# LED_Driver_-_4.net
KiCad netlist of a schematic drawn in Altium Designer
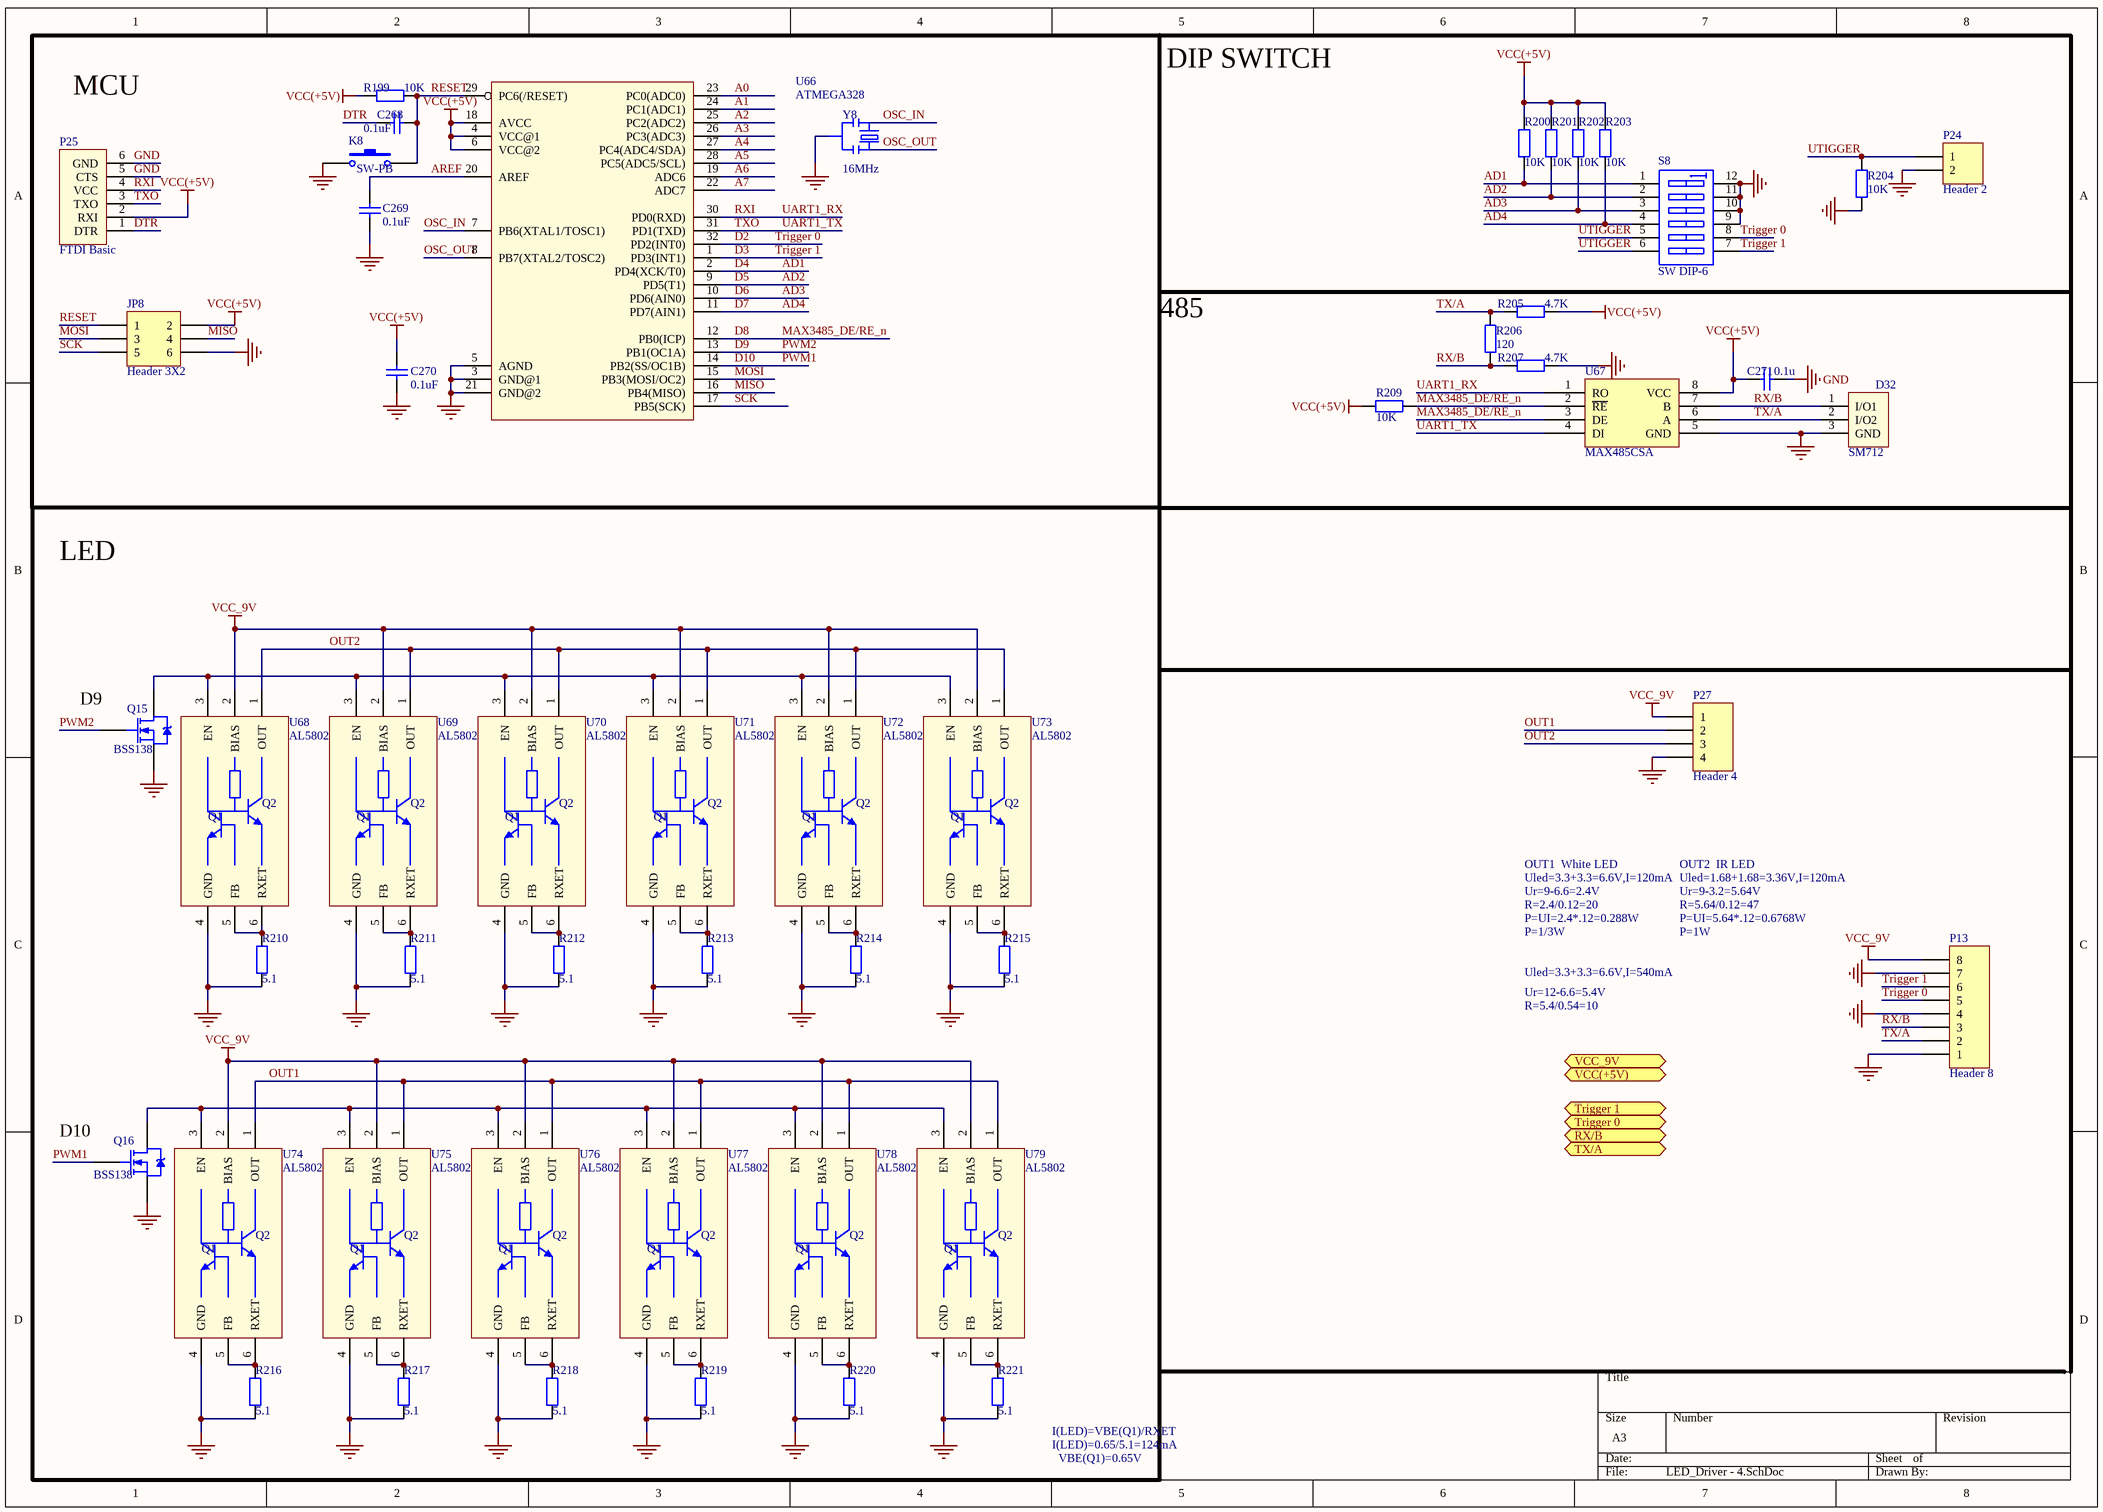
[diagram p0: LED_Driver - 4.SchDoc]

(export (version "E")
  (design (tool "Eeschema 10.0.6"))
  (components
    (comp (ref "C268")
      (value "0.1uF")
      (footprint "C0603")
      (description "Capacitor")
      (fields (field (name "IPARTNUMBER") "C100nF25V10%X7R") (field (name "VOLTAGE") "25V"))
      (libsource (lib "Schlib1") (part "CAP SMT C100nF25V10%X7R"))
    )
    (comp (ref "C269")
      (value "0.1uF")
      (footprint "C0603")
      (description "Capacitor")
      (fields (field (name "IPARTNUMBER") "C100nF25V10%X7R") (field (name "VOLTAGE") "25V"))
      (libsource (lib "Schlib1") (part "CAP SMT C100nF25V10%X7R"))
    )
    (comp (ref "C270")
      (value "0.1uF")
      (footprint "C0603")
      (description "Capacitor")
      (fields (field (name "IPARTNUMBER") "C100nF25V10%X7R") (field (name "VOLTAGE") "25V"))
      (libsource (lib "Schlib1") (part "CAP SMT C100nF25V10%X7R"))
    )
    (comp (ref "C271")
      (value "0.1u")
      (footprint "C0603")
      (description "Capacitor")
      (fields (field (name "PUBLISHER") "Altium Limited"))
      (libsource (lib "Miscellaneous Devices") (part "Cap"))
    )
    (comp (ref "D32")
      (value "SM712")
      (footprint "SOT23-3")
      (libsource (lib "STM32F4_CAM V2.0") (part "SM712"))
    )
    (comp (ref "JP8")
      (value "Header 3X2")
      (footprint "MHDR1X6")
      (description "Header, 3-Pin, Dual row")
      (fields (field (name "PUBLISHER") "Altium Limited"))
      (libsource (lib "Miscellaneous Connectors") (part "Header 3X2"))
    )
    (comp (ref "K8")
      (value "SW-PB")
      (footprint "157SW")
      (description "Switch")
      (fields (field (name "PUBLISHER") "Altium Limited"))
      (libsource (lib "Miscellaneous Devices") (part "SW-PB"))
    )
    (comp (ref "P13")
      (value "Header 8")
      (footprint "SH_1.25MM*8")
      (description "Header, 8-Pin")
      (fields (field (name "PUBLISHER") "Altium Limited"))
      (libsource (lib "Miscellaneous Connectors") (part "Header 8"))
    )
    (comp (ref "P24")
      (value "Header 2")
      (footprint "HDR1X2")
      (description "Header, 2-Pin")
      (fields (field (name "PUBLISHER") "Altium Limited"))
      (libsource (lib "Miscellaneous Connectors") (part "Header 2"))
    )
    (comp (ref "P25")
      (value "FTDI Basic")
      (footprint "MHDR1X6")
      (libsource (lib "PCB_Project1") (part "ARDUINO_SERIAL_PROGRAMPTH"))
    )
    (comp (ref "P27")
      (value "Header 4")
      (footprint "SMT_1.25MM*4")
      (description "Header, 4-Pin")
      (fields (field (name "PUBLISHER") "Altium Limited"))
      (libsource (lib "Miscellaneous Connectors") (part "Header 4"))
    )
    (comp (ref "Q15")
      (value "BSS138")
      (footprint "SOT-23 (Standard)")
      (fields
        (field (name "MANUFACTURER") "Fairchild Semiconductor")
        (field (name "MANUFACTURER PART NUMBER") "BSS123")
      )
      (libsource (lib "Miscellaneous_Devices") (part "NMOS"))
    )
    (comp (ref "Q16")
      (value "BSS138")
      (footprint "SOT-23 (Standard)")
      (fields
        (field (name "MANUFACTURER") "Fairchild Semiconductor")
        (field (name "MANUFACTURER PART NUMBER") "BSS123")
      )
      (libsource (lib "Miscellaneous_Devices") (part "NMOS"))
    )
    (comp (ref "R199")
      (value "10K")
      (footprint "R0603")
      (description "Resistor")
      (libsource (lib "") (part "Res2_2"))
    )
    (comp (ref "R200")
      (value "10K")
      (footprint "R0603")
      (description "Resistor")
      (libsource (lib "") (part "Res2_1"))
    )
    (comp (ref "R201")
      (value "10K")
      (footprint "R0603")
      (description "Resistor")
      (libsource (lib "") (part "Res2_1"))
    )
    (comp (ref "R202")
      (value "10K")
      (footprint "R0603")
      (description "Resistor")
      (libsource (lib "") (part "Res2_1"))
    )
    (comp (ref "R203")
      (value "10K")
      (footprint "R0603")
      (description "Resistor")
      (libsource (lib "") (part "Res2_1"))
    )
    (comp (ref "R204")
      (value "10K")
      (footprint "R0603")
      (description "Resistor")
      (fields (field (name "PUBLISHER") "Altium Limited"))
      (libsource (lib "Miscellaneous Devices") (part "Res2"))
    )
    (comp (ref "R205")
      (value "4.7K")
      (footprint "R0603")
      (description "Resistor")
      (libsource (lib "DM642") (part "Res2"))
    )
    (comp (ref "R206")
      (value "120")
      (footprint "R0603")
      (description "Resistor")
      (libsource (lib "") (part "Res2_1"))
    )
    (comp (ref "R207")
      (value "4.7K")
      (footprint "R0603")
      (description "Resistor")
      (libsource (lib "DM642") (part "Res2"))
    )
    (comp (ref "R209")
      (value "10K")
      (footprint "R0603")
      (description "Resistor")
      (libsource (lib "DM642") (part "Res2"))
    )
    (comp (ref "R210")
      (value "5.1")
      (footprint "R0603")
      (description "Resistor")
      (libsource (lib "") (part "Res2_1"))
    )
    (comp (ref "R211")
      (value "5.1")
      (footprint "R0603")
      (description "Resistor")
      (libsource (lib "") (part "Res2_1"))
    )
    (comp (ref "R212")
      (value "5.1")
      (footprint "R0603")
      (description "Resistor")
      (libsource (lib "") (part "Res2_1"))
    )
    (comp (ref "R213")
      (value "5.1")
      (footprint "R0603")
      (description "Resistor")
      (libsource (lib "") (part "Res2_1"))
    )
    (comp (ref "R214")
      (value "5.1")
      (footprint "R0603")
      (description "Resistor")
      (libsource (lib "") (part "Res2_1"))
    )
    (comp (ref "R215")
      (value "5.1")
      (footprint "R0603")
      (description "Resistor")
      (libsource (lib "") (part "Res2_1"))
    )
    (comp (ref "R216")
      (value "5.1")
      (footprint "R0603")
      (description "Resistor")
      (libsource (lib "") (part "Res2_1"))
    )
    (comp (ref "R217")
      (value "5.1")
      (footprint "R0603")
      (description "Resistor")
      (libsource (lib "") (part "Res2_1"))
    )
    (comp (ref "R218")
      (value "5.1")
      (footprint "R0603")
      (description "Resistor")
      (libsource (lib "") (part "Res2_1"))
    )
    (comp (ref "R219")
      (value "5.1")
      (footprint "R0603")
      (description "Resistor")
      (libsource (lib "") (part "Res2_1"))
    )
    (comp (ref "R220")
      (value "5.1")
      (footprint "R0603")
      (description "Resistor")
      (libsource (lib "") (part "Res2_1"))
    )
    (comp (ref "R221")
      (value "5.1")
      (footprint "R0603")
      (description "Resistor")
      (libsource (lib "") (part "Res2_1"))
    )
    (comp (ref "S8")
      (value "SW DIP-6")
      (footprint "DIP_SW_6WAY_SMD")
      (description "DIP Switch, 6 Position, SPST")
      (fields (field (name "PUBLISHER") "Altium Limited"))
      (libsource (lib "Miscellaneous Devices") (part "SW DIP-6"))
    )
    (comp (ref "U66")
      (value "ATMEGA328")
      (footprint "TQFP32-08")
      (libsource (lib "PCB_Project1") (part "ATMEGA168"))
    )
    (comp (ref "U67")
      (value "MAX485CSA")
      (footprint "SOIC-8")
      (libsource (lib "STM32F4_CAM V1.2") (part "MAX3485CSA"))
    )
    (comp (ref "U68") (value "AL5802") (footprint "SOT26") (libsource (lib "LED") (part "AL5802")))
    (comp (ref "U69") (value "AL5802") (footprint "SOT26") (libsource (lib "LED") (part "AL5802")))
    (comp (ref "U70") (value "AL5802") (footprint "SOT26") (libsource (lib "LED") (part "AL5802")))
    (comp (ref "U71") (value "AL5802") (footprint "SOT26") (libsource (lib "LED") (part "AL5802")))
    (comp (ref "U72") (value "AL5802") (footprint "SOT26") (libsource (lib "LED") (part "AL5802")))
    (comp (ref "U73") (value "AL5802") (footprint "SOT26") (libsource (lib "LED") (part "AL5802")))
    (comp (ref "U74") (value "AL5802") (footprint "SOT26") (libsource (lib "LED") (part "AL5802")))
    (comp (ref "U75") (value "AL5802") (footprint "SOT26") (libsource (lib "LED") (part "AL5802")))
    (comp (ref "U76") (value "AL5802") (footprint "SOT26") (libsource (lib "LED") (part "AL5802")))
    (comp (ref "U77") (value "AL5802") (footprint "SOT26") (libsource (lib "LED") (part "AL5802")))
    (comp (ref "U78") (value "AL5802") (footprint "SOT26") (libsource (lib "LED") (part "AL5802")))
    (comp (ref "U79") (value "AL5802") (footprint "SOT26") (libsource (lib "LED") (part "AL5802")))
    (comp (ref "Y8")
      (value "16MHz")
      (footprint "RESONATOR-SMD")
      (libsource (lib "SparkFun") (part "RESONATORSMD"))
    )
  )
  (nets
    (net (code "1") (name "/A0") (class "Default")
      (node (ref "U66") (pin "23") (pinfunction "PC0(ADC0)_23") (pintype "passive"))
    )
    (net (code "2") (name "/A1") (class "Default")
      (node (ref "U66") (pin "24") (pinfunction "PC1(ADC1)_24") (pintype "passive"))
    )
    (net (code "3") (name "/A2") (class "Default")
      (node (ref "U66") (pin "25") (pinfunction "PC2(ADC2)_25") (pintype "passive"))
    )
    (net (code "4") (name "/A3") (class "Default")
      (node (ref "U66") (pin "26") (pinfunction "PC3(ADC3)_26") (pintype "passive"))
    )
    (net (code "5") (name "/A4") (class "Default")
      (node (ref "U66") (pin "27") (pinfunction "PC4(ADC4/SDA)_27") (pintype "passive"))
    )
    (net (code "6") (name "/A5") (class "Default")
      (node (ref "U66") (pin "28") (pinfunction "PC5(ADC5/SCL)_28") (pintype "passive"))
    )
    (net (code "7") (name "/A6") (class "Default")
      (node (ref "U66") (pin "19") (pinfunction "ADC6_19") (pintype "passive"))
    )
    (net (code "8") (name "/A7") (class "Default")
      (node (ref "U66") (pin "22") (pinfunction "ADC7_22") (pintype "passive"))
    )
    (net (code "9") (name "/AD1") (class "Default")
      (node (ref "R200") (pin "2") (pinfunction "2_2") (pintype "passive"))
      (node (ref "S8") (pin "1") (pinfunction "A1_1") (pintype "passive"))
      (node (ref "U66") (pin "2") (pinfunction "PD4(XCK/T0)_2") (pintype "passive"))
    )
    (net (code "10") (name "/AD2") (class "Default")
      (node (ref "R201") (pin "2") (pinfunction "2_2") (pintype "passive"))
      (node (ref "S8") (pin "2") (pinfunction "A2_2") (pintype "passive"))
      (node (ref "U66") (pin "9") (pinfunction "PD5(T1)_9") (pintype "passive"))
    )
    (net (code "11") (name "/AD3") (class "Default")
      (node (ref "R202") (pin "2") (pinfunction "2_2") (pintype "passive"))
      (node (ref "S8") (pin "3") (pinfunction "A3_3") (pintype "passive"))
      (node (ref "U66") (pin "10") (pinfunction "PD6(AIN0)_10") (pintype "passive"))
    )
    (net (code "12") (name "/AD4") (class "Default")
      (node (ref "R203") (pin "2") (pinfunction "2_2") (pintype "passive"))
      (node (ref "S8") (pin "4") (pinfunction "A4_4") (pintype "passive"))
      (node (ref "U66") (pin "11") (pinfunction "PD7(AIN1)_11") (pintype "passive"))
    )
    (net (code "13") (name "/AREF") (class "Default")
      (node (ref "C269") (pin "2") (pinfunction "2_2") (pintype "passive"))
      (node (ref "U66") (pin "20") (pinfunction "AREF_20") (pintype "passive"))
    )
    (net (code "14") (name "/D2") (class "Default")
      (node (ref "P13") (pin "5") (pinfunction "5_5") (pintype "passive"))
      (node (ref "S8") (pin "8") (pinfunction "B5_8") (pintype "passive"))
      (node (ref "U66") (pin "32") (pinfunction "PD2(INT0)_32") (pintype "passive"))
    )
    (net (code "15") (name "/D3") (class "Default")
      (node (ref "P13") (pin "6") (pinfunction "6_6") (pintype "passive"))
      (node (ref "S8") (pin "7") (pinfunction "B6_7") (pintype "passive"))
      (node (ref "U66") (pin "1") (pinfunction "PD3(INT1)_1") (pintype "passive"))
    )
    (net (code "16") (name "/D8") (class "Default")
      (node (ref "R209") (pin "1") (pinfunction "1_1") (pintype "passive"))
      (node (ref "U66") (pin "12") (pinfunction "PB0(ICP)_12") (pintype "passive"))
      (node (ref "U67") (pin "2") (pinfunction "~{RE}_2") (pintype "passive"))
      (node (ref "U67") (pin "3") (pinfunction "DE_3") (pintype "passive"))
    )
    (net (code "17") (name "/D9") (class "Default")
      (node (ref "Q15") (pin "G") (pinfunction "G_G") (pintype "passive"))
      (node (ref "U66") (pin "13") (pinfunction "PB1(OC1A)_13") (pintype "passive"))
    )
    (net (code "18") (name "/D10") (class "Default")
      (node (ref "Q16") (pin "G") (pinfunction "G_G") (pintype "passive"))
      (node (ref "U66") (pin "14") (pinfunction "PB2(SS/OC1B)_14") (pintype "passive"))
    )
    (net (code "19") (name "/DTR") (class "Default")
      (node (ref "C268") (pin "1") (pinfunction "1_1") (pintype "passive"))
      (node (ref "P25") (pin "1") (pinfunction "DTR_1") (pintype "passive"))
    )
    (net (code "20") (name "/MISO") (class "Default")
      (node (ref "JP8") (pin "4") (pinfunction "4_4") (pintype "passive"))
      (node (ref "U66") (pin "16") (pinfunction "PB4(MISO)_16") (pintype "passive"))
    )
    (net (code "21") (name "/MOSI") (class "Default")
      (node (ref "JP8") (pin "3") (pinfunction "3_3") (pintype "passive"))
      (node (ref "U66") (pin "15") (pinfunction "PB3(MOSI/OC2)_15") (pintype "passive"))
    )
    (net (code "22") (name "/OSC_IN") (class "Default")
      (node (ref "U66") (pin "7") (pinfunction "PB6(XTAL1/TOSC1)_7") (pintype "passive"))
      (node (ref "Y8") (pin "3") (pinfunction "3_3") (pintype "passive"))
    )
    (net (code "23") (name "/OSC_OUT") (class "Default")
      (node (ref "U66") (pin "8") (pinfunction "PB7(XTAL2/TOSC2)_8") (pintype "passive"))
      (node (ref "Y8") (pin "1") (pinfunction "1_1") (pintype "passive"))
    )
    (net (code "24") (name "/OUT1") (class "Default")
      (node (ref "P27") (pin "2") (pinfunction "2_2") (pintype "passive"))
      (node (ref "U74") (pin "1") (pinfunction "OUT_1") (pintype "passive"))
      (node (ref "U75") (pin "1") (pinfunction "OUT_1") (pintype "passive"))
      (node (ref "U76") (pin "1") (pinfunction "OUT_1") (pintype "passive"))
      (node (ref "U77") (pin "1") (pinfunction "OUT_1") (pintype "passive"))
      (node (ref "U78") (pin "1") (pinfunction "OUT_1") (pintype "passive"))
      (node (ref "U79") (pin "1") (pinfunction "OUT_1") (pintype "passive"))
    )
    (net (code "25") (name "/OUT2") (class "Default")
      (node (ref "P27") (pin "3") (pinfunction "3_3") (pintype "passive"))
      (node (ref "U68") (pin "1") (pinfunction "OUT_1") (pintype "passive"))
      (node (ref "U69") (pin "1") (pinfunction "OUT_1") (pintype "passive"))
      (node (ref "U70") (pin "1") (pinfunction "OUT_1") (pintype "passive"))
      (node (ref "U71") (pin "1") (pinfunction "OUT_1") (pintype "passive"))
      (node (ref "U72") (pin "1") (pinfunction "OUT_1") (pintype "passive"))
      (node (ref "U73") (pin "1") (pinfunction "OUT_1") (pintype "passive"))
    )
    (net (code "26") (name "/RESET") (class "Default")
      (node (ref "C268") (pin "2") (pinfunction "2_2") (pintype "passive"))
      (node (ref "JP8") (pin "1") (pinfunction "1_1") (pintype "passive"))
      (node (ref "K8") (pin "2") (pinfunction "2_2") (pintype "passive"))
      (node (ref "R199") (pin "2") (pinfunction "2_2") (pintype "passive"))
      (node (ref "U66") (pin "29") (pinfunction "PC6(/RESET)_29") (pintype "passive"))
    )
    (net (code "27") (name "/RXI") (class "Default")
      (node (ref "P25") (pin "4") (pinfunction "VCC_4") (pintype "passive"))
      (node (ref "U66") (pin "30") (pinfunction "PD0(RXD)_30") (pintype "passive"))
      (node (ref "U67") (pin "1") (pinfunction "RO_1") (pintype "passive"))
    )
    (net (code "28") (name "/RX{slash}B") (class "Default")
      (node (ref "D32") (pin "1") (pinfunction "I/O1_1") (pintype "passive"))
      (node (ref "P13") (pin "3") (pinfunction "3_3") (pintype "passive"))
      (node (ref "R206") (pin "2") (pinfunction "2_2") (pintype "passive"))
      (node (ref "R207") (pin "2") (pinfunction "2_2") (pintype "passive"))
      (node (ref "U67") (pin "7") (pinfunction "B_7") (pintype "passive"))
    )
    (net (code "29") (name "/SCK") (class "Default")
      (node (ref "JP8") (pin "5") (pinfunction "5_5") (pintype "passive"))
      (node (ref "U66") (pin "17") (pinfunction "PB5(SCK)_17") (pintype "passive"))
    )
    (net (code "30") (name "/TXO") (class "Default")
      (node (ref "P25") (pin "3") (pinfunction "TXO_3") (pintype "passive"))
      (node (ref "U66") (pin "31") (pinfunction "PD1(TXD)_31") (pintype "passive"))
      (node (ref "U67") (pin "4") (pinfunction "DI_4") (pintype "passive"))
    )
    (net (code "31") (name "/TX{slash}A") (class "Default")
      (node (ref "D32") (pin "2") (pinfunction "I/O2_2") (pintype "passive"))
      (node (ref "P13") (pin "2") (pinfunction "2_2") (pintype "passive"))
      (node (ref "R205") (pin "2") (pinfunction "2_2") (pintype "passive"))
      (node (ref "R206") (pin "1") (pinfunction "1_1") (pintype "passive"))
      (node (ref "U67") (pin "6") (pinfunction "A_6") (pintype "passive"))
    )
    (net (code "32") (name "/UTIGGER") (class "Default")
      (node (ref "P24") (pin "1") (pinfunction "1_1") (pintype "passive"))
      (node (ref "R204") (pin "2") (pinfunction "2_2") (pintype "passive"))
      (node (ref "S8") (pin "5") (pinfunction "A5_5") (pintype "passive"))
      (node (ref "S8") (pin "6") (pinfunction "A6_6") (pintype "passive"))
    )
    (net (code "33") (name "GND") (class "Default")
      (node (ref "C269") (pin "1") (pinfunction "1_1") (pintype "passive"))
      (node (ref "C270") (pin "2") (pinfunction "2_2") (pintype "passive"))
      (node (ref "C271") (pin "1") (pinfunction "1_1") (pintype "passive"))
      (node (ref "D32") (pin "3") (pinfunction "GND_3") (pintype "passive"))
      (node (ref "JP8") (pin "6") (pinfunction "6_6") (pintype "passive"))
      (node (ref "K8") (pin "1") (pinfunction "1_1") (pintype "passive"))
      (node (ref "P13") (pin "1") (pinfunction "1_1") (pintype "passive"))
      (node (ref "P13") (pin "4") (pinfunction "4_4") (pintype "passive"))
      (node (ref "P13") (pin "7") (pinfunction "7_7") (pintype "passive"))
      (node (ref "P24") (pin "2") (pinfunction "2_2") (pintype "passive"))
      (node (ref "P25") (pin "5") (pinfunction "CTS_5") (pintype "passive"))
      (node (ref "P25") (pin "6") (pinfunction "GND_6") (pintype "passive"))
      (node (ref "P27") (pin "4") (pinfunction "4_4") (pintype "passive"))
      (node (ref "Q15") (pin "S") (pinfunction "S_S") (pintype "passive"))
      (node (ref "Q16") (pin "S") (pinfunction "S_S") (pintype "passive"))
      (node (ref "R204") (pin "1") (pinfunction "1_1") (pintype "passive"))
      (node (ref "R207") (pin "1") (pinfunction "1_1") (pintype "passive"))
      (node (ref "R210") (pin "2") (pinfunction "2_2") (pintype "passive"))
      (node (ref "R211") (pin "2") (pinfunction "2_2") (pintype "passive"))
      (node (ref "R212") (pin "2") (pinfunction "2_2") (pintype "passive"))
      (node (ref "R213") (pin "2") (pinfunction "2_2") (pintype "passive"))
      (node (ref "R214") (pin "2") (pinfunction "2_2") (pintype "passive"))
      (node (ref "R215") (pin "2") (pinfunction "2_2") (pintype "passive"))
      (node (ref "R216") (pin "2") (pinfunction "2_2") (pintype "passive"))
      (node (ref "R217") (pin "2") (pinfunction "2_2") (pintype "passive"))
      (node (ref "R218") (pin "2") (pinfunction "2_2") (pintype "passive"))
      (node (ref "R219") (pin "2") (pinfunction "2_2") (pintype "passive"))
      (node (ref "R220") (pin "2") (pinfunction "2_2") (pintype "passive"))
      (node (ref "R221") (pin "2") (pinfunction "2_2") (pintype "passive"))
      (node (ref "S8") (pin "10") (pinfunction "B3_10") (pintype "passive"))
      (node (ref "S8") (pin "11") (pinfunction "B2_11") (pintype "passive"))
      (node (ref "S8") (pin "12") (pinfunction "B1_12") (pintype "passive"))
      (node (ref "S8") (pin "9") (pinfunction "B4_9") (pintype "passive"))
      (node (ref "U66") (pin "21") (pinfunction "GND@2_21") (pintype "passive"))
      (node (ref "U66") (pin "3") (pinfunction "GND@1_3") (pintype "passive"))
      (node (ref "U66") (pin "5") (pinfunction "AGND_5") (pintype "passive"))
      (node (ref "U67") (pin "5") (pinfunction "GND_5") (pintype "passive"))
      (node (ref "U68") (pin "4") (pinfunction "GND_4") (pintype "passive"))
      (node (ref "U69") (pin "4") (pinfunction "GND_4") (pintype "passive"))
      (node (ref "U70") (pin "4") (pinfunction "GND_4") (pintype "passive"))
      (node (ref "U71") (pin "4") (pinfunction "GND_4") (pintype "passive"))
      (node (ref "U72") (pin "4") (pinfunction "GND_4") (pintype "passive"))
      (node (ref "U73") (pin "4") (pinfunction "GND_4") (pintype "passive"))
      (node (ref "U74") (pin "4") (pinfunction "GND_4") (pintype "passive"))
      (node (ref "U75") (pin "4") (pinfunction "GND_4") (pintype "passive"))
      (node (ref "U76") (pin "4") (pinfunction "GND_4") (pintype "passive"))
      (node (ref "U77") (pin "4") (pinfunction "GND_4") (pintype "passive"))
      (node (ref "U78") (pin "4") (pinfunction "GND_4") (pintype "passive"))
      (node (ref "U79") (pin "4") (pinfunction "GND_4") (pintype "passive"))
      (node (ref "Y8") (pin "2") (pinfunction "2_2") (pintype "passive"))
    )
    (net (code "34") (name "Net-(U68-EN)") (class "Default")
      (node (ref "Q15") (pin "D") (pinfunction "D_D") (pintype "passive"))
      (node (ref "U68") (pin "3") (pinfunction "EN_3") (pintype "passive"))
      (node (ref "U69") (pin "3") (pinfunction "EN_3") (pintype "passive"))
      (node (ref "U70") (pin "3") (pinfunction "EN_3") (pintype "passive"))
      (node (ref "U71") (pin "3") (pinfunction "EN_3") (pintype "passive"))
      (node (ref "U72") (pin "3") (pinfunction "EN_3") (pintype "passive"))
      (node (ref "U73") (pin "3") (pinfunction "EN_3") (pintype "passive"))
    )
    (net (code "35") (name "Net-(U68-FB)") (class "Default")
      (node (ref "R210") (pin "1") (pinfunction "1_1") (pintype "passive"))
      (node (ref "U68") (pin "5") (pinfunction "FB_5") (pintype "passive"))
      (node (ref "U68") (pin "6") (pinfunction "RXET_6") (pintype "passive"))
    )
    (net (code "36") (name "Net-(U69-FB)") (class "Default")
      (node (ref "R211") (pin "1") (pinfunction "1_1") (pintype "passive"))
      (node (ref "U69") (pin "5") (pinfunction "FB_5") (pintype "passive"))
      (node (ref "U69") (pin "6") (pinfunction "RXET_6") (pintype "passive"))
    )
    (net (code "37") (name "Net-(U70-FB)") (class "Default")
      (node (ref "R212") (pin "1") (pinfunction "1_1") (pintype "passive"))
      (node (ref "U70") (pin "5") (pinfunction "FB_5") (pintype "passive"))
      (node (ref "U70") (pin "6") (pinfunction "RXET_6") (pintype "passive"))
    )
    (net (code "38") (name "Net-(U71-FB)") (class "Default")
      (node (ref "R213") (pin "1") (pinfunction "1_1") (pintype "passive"))
      (node (ref "U71") (pin "5") (pinfunction "FB_5") (pintype "passive"))
      (node (ref "U71") (pin "6") (pinfunction "RXET_6") (pintype "passive"))
    )
    (net (code "39") (name "Net-(U72-FB)") (class "Default")
      (node (ref "R214") (pin "1") (pinfunction "1_1") (pintype "passive"))
      (node (ref "U72") (pin "5") (pinfunction "FB_5") (pintype "passive"))
      (node (ref "U72") (pin "6") (pinfunction "RXET_6") (pintype "passive"))
    )
    (net (code "40") (name "Net-(U73-FB)") (class "Default")
      (node (ref "R215") (pin "1") (pinfunction "1_1") (pintype "passive"))
      (node (ref "U73") (pin "5") (pinfunction "FB_5") (pintype "passive"))
      (node (ref "U73") (pin "6") (pinfunction "RXET_6") (pintype "passive"))
    )
    (net (code "41") (name "Net-(U74-EN)") (class "Default")
      (node (ref "Q16") (pin "D") (pinfunction "D_D") (pintype "passive"))
      (node (ref "U74") (pin "3") (pinfunction "EN_3") (pintype "passive"))
      (node (ref "U75") (pin "3") (pinfunction "EN_3") (pintype "passive"))
      (node (ref "U76") (pin "3") (pinfunction "EN_3") (pintype "passive"))
      (node (ref "U77") (pin "3") (pinfunction "EN_3") (pintype "passive"))
      (node (ref "U78") (pin "3") (pinfunction "EN_3") (pintype "passive"))
      (node (ref "U79") (pin "3") (pinfunction "EN_3") (pintype "passive"))
    )
    (net (code "42") (name "Net-(U74-FB)") (class "Default")
      (node (ref "R216") (pin "1") (pinfunction "1_1") (pintype "passive"))
      (node (ref "U74") (pin "5") (pinfunction "FB_5") (pintype "passive"))
      (node (ref "U74") (pin "6") (pinfunction "RXET_6") (pintype "passive"))
    )
    (net (code "43") (name "Net-(U75-FB)") (class "Default")
      (node (ref "R217") (pin "1") (pinfunction "1_1") (pintype "passive"))
      (node (ref "U75") (pin "5") (pinfunction "FB_5") (pintype "passive"))
      (node (ref "U75") (pin "6") (pinfunction "RXET_6") (pintype "passive"))
    )
    (net (code "44") (name "Net-(U76-FB)") (class "Default")
      (node (ref "R218") (pin "1") (pinfunction "1_1") (pintype "passive"))
      (node (ref "U76") (pin "5") (pinfunction "FB_5") (pintype "passive"))
      (node (ref "U76") (pin "6") (pinfunction "RXET_6") (pintype "passive"))
    )
    (net (code "45") (name "Net-(U77-FB)") (class "Default")
      (node (ref "R219") (pin "1") (pinfunction "1_1") (pintype "passive"))
      (node (ref "U77") (pin "5") (pinfunction "FB_5") (pintype "passive"))
      (node (ref "U77") (pin "6") (pinfunction "RXET_6") (pintype "passive"))
    )
    (net (code "46") (name "Net-(U78-FB)") (class "Default")
      (node (ref "R220") (pin "1") (pinfunction "1_1") (pintype "passive"))
      (node (ref "U78") (pin "5") (pinfunction "FB_5") (pintype "passive"))
      (node (ref "U78") (pin "6") (pinfunction "RXET_6") (pintype "passive"))
    )
    (net (code "47") (name "Net-(U79-FB)") (class "Default")
      (node (ref "R221") (pin "1") (pinfunction "1_1") (pintype "passive"))
      (node (ref "U79") (pin "5") (pinfunction "FB_5") (pintype "passive"))
      (node (ref "U79") (pin "6") (pinfunction "RXET_6") (pintype "passive"))
    )
    (net (code "48") (name "VCC(+5V)") (class "Default")
      (node (ref "C270") (pin "1") (pinfunction "1_1") (pintype "passive"))
      (node (ref "C271") (pin "2") (pinfunction "2_2") (pintype "passive"))
      (node (ref "JP8") (pin "2") (pinfunction "2_2") (pintype "passive"))
      (node (ref "P25") (pin "2") (pinfunction "RXI_2") (pintype "passive"))
      (node (ref "R199") (pin "1") (pinfunction "1_1") (pintype "passive"))
      (node (ref "R200") (pin "1") (pinfunction "1_1") (pintype "passive"))
      (node (ref "R201") (pin "1") (pinfunction "1_1") (pintype "passive"))
      (node (ref "R202") (pin "1") (pinfunction "1_1") (pintype "passive"))
      (node (ref "R203") (pin "1") (pinfunction "1_1") (pintype "passive"))
      (node (ref "R205") (pin "1") (pinfunction "1_1") (pintype "passive"))
      (node (ref "R209") (pin "2") (pinfunction "2_2") (pintype "passive"))
      (node (ref "U66") (pin "18") (pinfunction "AVCC_18") (pintype "passive"))
      (node (ref "U66") (pin "4") (pinfunction "VCC@1_4") (pintype "passive"))
      (node (ref "U66") (pin "6") (pinfunction "VCC@2_6") (pintype "passive"))
      (node (ref "U67") (pin "8") (pinfunction "VCC_8") (pintype "passive"))
    )
    (net (code "49") (name "VCC_9V") (class "Default")
      (node (ref "P13") (pin "8") (pinfunction "8_8") (pintype "passive"))
      (node (ref "P27") (pin "1") (pinfunction "1_1") (pintype "passive"))
      (node (ref "U68") (pin "2") (pinfunction "BIAS_2") (pintype "passive"))
      (node (ref "U69") (pin "2") (pinfunction "BIAS_2") (pintype "passive"))
      (node (ref "U70") (pin "2") (pinfunction "BIAS_2") (pintype "passive"))
      (node (ref "U71") (pin "2") (pinfunction "BIAS_2") (pintype "passive"))
      (node (ref "U72") (pin "2") (pinfunction "BIAS_2") (pintype "passive"))
      (node (ref "U73") (pin "2") (pinfunction "BIAS_2") (pintype "passive"))
      (node (ref "U74") (pin "2") (pinfunction "BIAS_2") (pintype "passive"))
      (node (ref "U75") (pin "2") (pinfunction "BIAS_2") (pintype "passive"))
      (node (ref "U76") (pin "2") (pinfunction "BIAS_2") (pintype "passive"))
      (node (ref "U77") (pin "2") (pinfunction "BIAS_2") (pintype "passive"))
      (node (ref "U78") (pin "2") (pinfunction "BIAS_2") (pintype "passive"))
      (node (ref "U79") (pin "2") (pinfunction "BIAS_2") (pintype "passive"))
    )
  )
)
